# 11-UWB-Main.net
KiCad netlist of a schematic drawn in Altium Designer
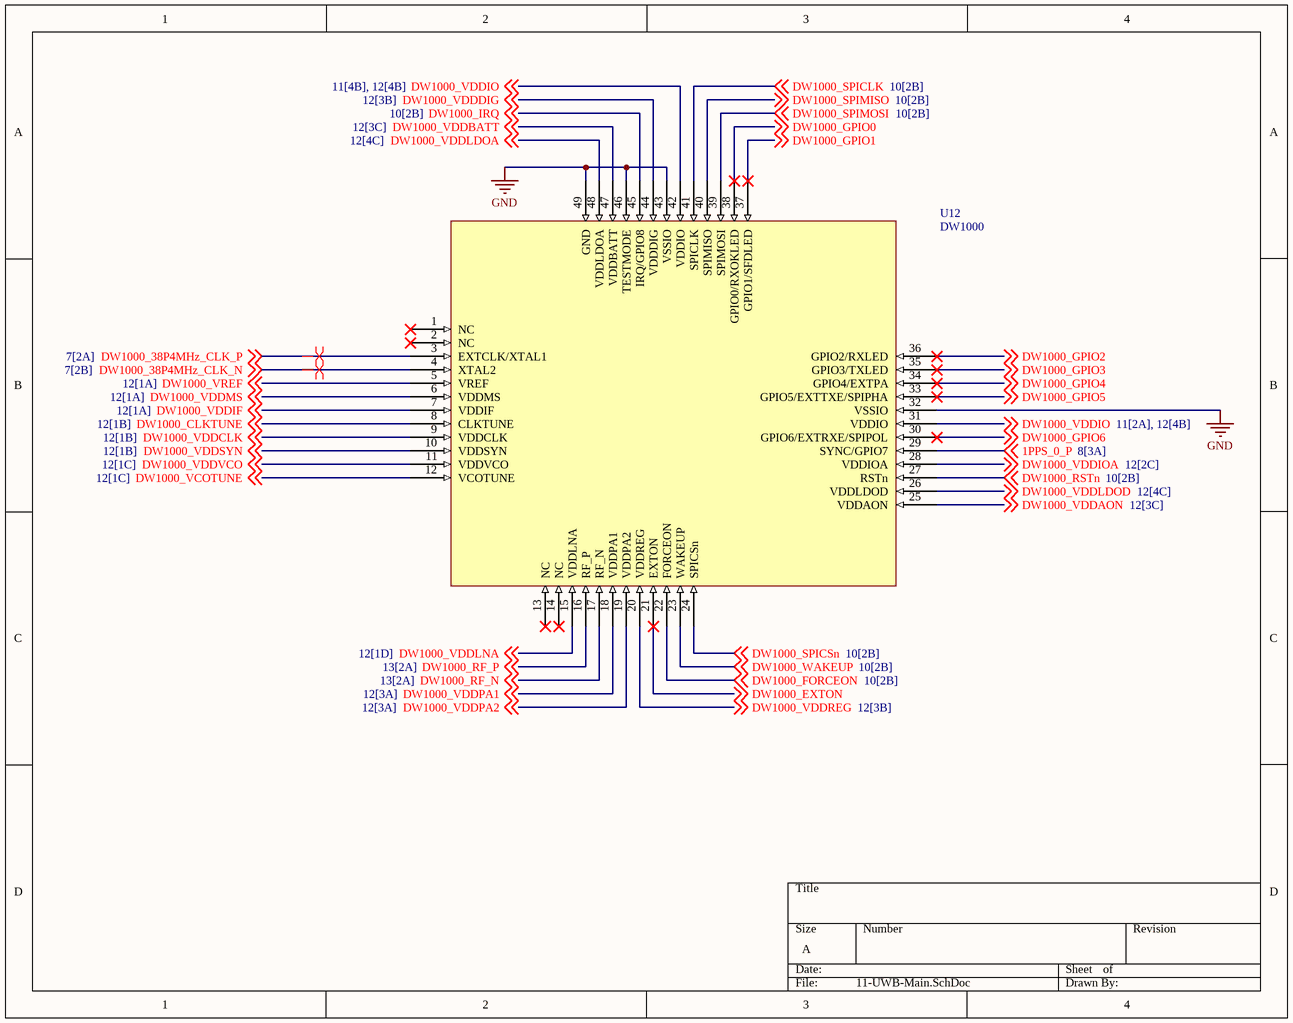
[diagram p0: 11-UWB-Main.SchDoc]

(export (version "E")
  (design (tool "Eeschema 10.0.6"))
  (components
    (comp (ref "U12")
      (value "DW1000")
      (footprint "DW1000_Footprint")
      (libsource (lib "TimeStick_Lib") (part "DW1000"))
    )
  )
  (nets
    (net (code "1") (name "1PPS_0_P") (class "Default")
      (node (ref "U12") (pin "29") (pinfunction "SYNC/GPIO7_29") (pintype "input"))
    )
    (net (code "2") (name "DW1000_38P4MHz_CLK_N") (class "Default")
      (node (ref "U12") (pin "4") (pinfunction "XTAL2_4") (pintype "input"))
    )
    (net (code "3") (name "DW1000_38P4MHz_CLK_P") (class "Default")
      (node (ref "U12") (pin "3") (pinfunction "EXTCLK/XTAL1_3") (pintype "input"))
    )
    (net (code "4") (name "DW1000_CLKTUNE") (class "Default")
      (node (ref "U12") (pin "8") (pinfunction "CLKTUNE_8") (pintype "input"))
    )
    (net (code "5") (name "DW1000_EXTON") (class "Default")
      (node (ref "U12") (pin "21") (pinfunction "EXTON_21") (pintype "input"))
    )
    (net (code "6") (name "DW1000_FORCEON") (class "Default")
      (node (ref "U12") (pin "22") (pinfunction "FORCEON_22") (pintype "input"))
    )
    (net (code "7") (name "DW1000_GPIO0") (class "Default")
      (node (ref "U12") (pin "38") (pinfunction "GPIO0/RXOKLED_38") (pintype "input"))
    )
    (net (code "8") (name "DW1000_GPIO1") (class "Default")
      (node (ref "U12") (pin "37") (pinfunction "GPIO1/SFDLED_37") (pintype "input"))
    )
    (net (code "9") (name "DW1000_GPIO2") (class "Default")
      (node (ref "U12") (pin "36") (pinfunction "GPIO2/RXLED_36") (pintype "input"))
    )
    (net (code "10") (name "DW1000_GPIO3") (class "Default")
      (node (ref "U12") (pin "35") (pinfunction "GPIO3/TXLED_35") (pintype "input"))
    )
    (net (code "11") (name "DW1000_GPIO4") (class "Default")
      (node (ref "U12") (pin "34") (pinfunction "GPIO4/EXTPA_34") (pintype "input"))
    )
    (net (code "12") (name "DW1000_GPIO5") (class "Default")
      (node (ref "U12") (pin "33") (pinfunction "GPIO5/EXTTXE/SPIPHA_33") (pintype "input"))
    )
    (net (code "13") (name "DW1000_GPIO6") (class "Default")
      (node (ref "U12") (pin "30") (pinfunction "GPIO6/EXTRXE/SPIPOL_30") (pintype "input"))
    )
    (net (code "14") (name "DW1000_IRQ") (class "Default")
      (node (ref "U12") (pin "45") (pinfunction "IRQ/GPIO8_45") (pintype "input"))
    )
    (net (code "15") (name "DW1000_RF_N") (class "Default")
      (node (ref "U12") (pin "17") (pinfunction "RF_N_17") (pintype "input"))
    )
    (net (code "16") (name "DW1000_RF_P") (class "Default")
      (node (ref "U12") (pin "16") (pinfunction "RF_P_16") (pintype "input"))
    )
    (net (code "17") (name "DW1000_RSTn") (class "Default")
      (node (ref "U12") (pin "27") (pinfunction "RSTn_27") (pintype "input"))
    )
    (net (code "18") (name "DW1000_SPICLK") (class "Default")
      (node (ref "U12") (pin "41") (pinfunction "SPICLK_41") (pintype "input"))
    )
    (net (code "19") (name "DW1000_SPICSn") (class "Default")
      (node (ref "U12") (pin "24") (pinfunction "SPICSn_24") (pintype "input"))
    )
    (net (code "20") (name "DW1000_SPIMISO") (class "Default")
      (node (ref "U12") (pin "40") (pinfunction "SPIMISO_40") (pintype "input"))
    )
    (net (code "21") (name "DW1000_SPIMOSI") (class "Default")
      (node (ref "U12") (pin "39") (pinfunction "SPIMOSI_39") (pintype "input"))
    )
    (net (code "22") (name "DW1000_VCOTUNE") (class "Default")
      (node (ref "U12") (pin "12") (pinfunction "VCOTUNE_12") (pintype "input"))
    )
    (net (code "23") (name "DW1000_VDDAON") (class "Default")
      (node (ref "U12") (pin "25") (pinfunction "VDDAON_25") (pintype "input"))
    )
    (net (code "24") (name "DW1000_VDDBATT") (class "Default")
      (node (ref "U12") (pin "47") (pinfunction "VDDBATT_47") (pintype "input"))
    )
    (net (code "25") (name "DW1000_VDDCLK") (class "Default")
      (node (ref "U12") (pin "9") (pinfunction "VDDCLK_9") (pintype "input"))
    )
    (net (code "26") (name "DW1000_VDDDIG") (class "Default")
      (node (ref "U12") (pin "44") (pinfunction "VDDDIG_44") (pintype "input"))
    )
    (net (code "27") (name "DW1000_VDDIF") (class "Default")
      (node (ref "U12") (pin "7") (pinfunction "VDDIF_7") (pintype "input"))
    )
    (net (code "28") (name "DW1000_VDDIO") (class "Default")
      (node (ref "U12") (pin "31") (pinfunction "VDDIO_31") (pintype "input"))
      (node (ref "U12") (pin "42") (pinfunction "VDDIO_42") (pintype "input"))
    )
    (net (code "29") (name "DW1000_VDDIOA") (class "Default")
      (node (ref "U12") (pin "28") (pinfunction "VDDIOA_28") (pintype "input"))
    )
    (net (code "30") (name "DW1000_VDDLDOA") (class "Default")
      (node (ref "U12") (pin "48") (pinfunction "VDDLDOA_48") (pintype "input"))
    )
    (net (code "31") (name "DW1000_VDDLDOD") (class "Default")
      (node (ref "U12") (pin "26") (pinfunction "VDDLDOD_26") (pintype "input"))
    )
    (net (code "32") (name "DW1000_VDDLNA") (class "Default")
      (node (ref "U12") (pin "15") (pinfunction "VDDLNA_15") (pintype "input"))
    )
    (net (code "33") (name "DW1000_VDDMS") (class "Default")
      (node (ref "U12") (pin "6") (pinfunction "VDDMS_6") (pintype "input"))
    )
    (net (code "34") (name "DW1000_VDDPA1") (class "Default")
      (node (ref "U12") (pin "18") (pinfunction "VDDPA1_18") (pintype "input"))
    )
    (net (code "35") (name "DW1000_VDDPA2") (class "Default")
      (node (ref "U12") (pin "19") (pinfunction "VDDPA2_19") (pintype "input"))
    )
    (net (code "36") (name "DW1000_VDDREG") (class "Default")
      (node (ref "U12") (pin "20") (pinfunction "VDDREG_20") (pintype "input"))
    )
    (net (code "37") (name "DW1000_VDDSYN") (class "Default")
      (node (ref "U12") (pin "10") (pinfunction "VDDSYN_10") (pintype "input"))
    )
    (net (code "38") (name "DW1000_VDDVCO") (class "Default")
      (node (ref "U12") (pin "11") (pinfunction "VDDVCO_11") (pintype "input"))
    )
    (net (code "39") (name "DW1000_VREF") (class "Default")
      (node (ref "U12") (pin "5") (pinfunction "VREF_5") (pintype "input"))
    )
    (net (code "40") (name "DW1000_WAKEUP") (class "Default")
      (node (ref "U12") (pin "23") (pinfunction "WAKEUP_23") (pintype "input"))
    )
    (net (code "41") (name "GND") (class "Default")
      (node (ref "U12") (pin "32") (pinfunction "VSSIO_32") (pintype "input"))
      (node (ref "U12") (pin "43") (pinfunction "VSSIO_43") (pintype "input"))
      (node (ref "U12") (pin "46") (pinfunction "TESTMODE_46") (pintype "input"))
      (node (ref "U12") (pin "49") (pinfunction "GND_49") (pintype "input"))
    )
    (net (code "42") (name "unconnected-(U12-NC-Pad1)") (class "Default")
      (node (ref "U12") (pin "1") (pinfunction "NC_1") (pintype "input+no_connect"))
    )
    (net (code "43") (name "unconnected-(U12-NC-Pad2)") (class "Default")
      (node (ref "U12") (pin "2") (pinfunction "NC_2") (pintype "input+no_connect"))
    )
    (net (code "44") (name "unconnected-(U12-NC-Pad13)") (class "Default")
      (node (ref "U12") (pin "13") (pinfunction "NC_13") (pintype "input+no_connect"))
    )
    (net (code "45") (name "unconnected-(U12-NC-Pad14)") (class "Default")
      (node (ref "U12") (pin "14") (pinfunction "NC_14") (pintype "input+no_connect"))
    )
  )
)
